# spider-som.net
KiCad netlist of a schematic drawn in Altium Designer
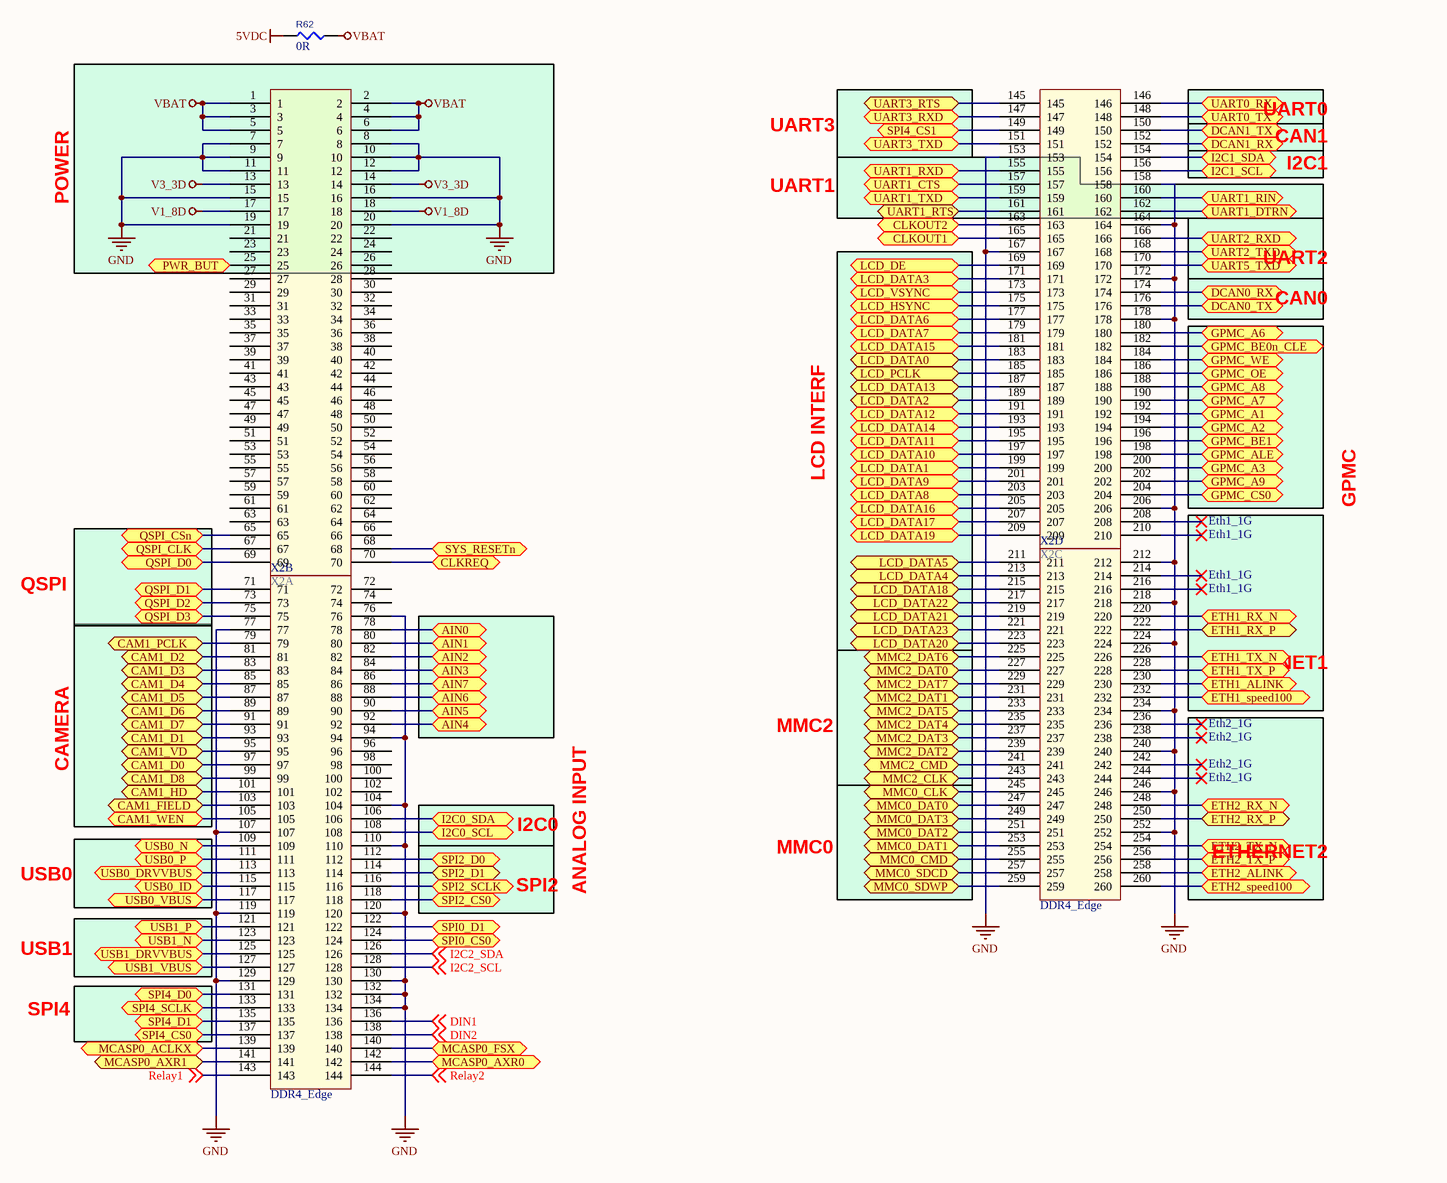
[diagram p0: spider-som.SchDoc]

(export (version "E")
  (design (tool "Eeschema 10.0.6"))
  (components
    (comp (ref "R62")
      (value "0R")
      (footprint "RESC1608X55N")
      (description "R0603")
      (libsource (lib "spider") (part "R0603"))
    )
    (comp (ref "X2")
      (value "DDR4_Edge")
      (footprint "DDR4 SO_DIMM connector")
      (description "DDR4 edge memory SO-DIMM connector, 260 pin")
      (libsource (lib "spider") (part "DDR4_Edge"))
    )
  )
  (nets
    (net (code "1") (name "/AIN0") (class "Default")
      (node (ref "X2") (pin "78") (pinfunction "78_78") (pintype "passive"))
    )
    (net (code "2") (name "/AIN1") (class "Default")
      (node (ref "X2") (pin "80") (pinfunction "80_80") (pintype "passive"))
    )
    (net (code "3") (name "/AIN2") (class "Default")
      (node (ref "X2") (pin "82") (pinfunction "82_82") (pintype "passive"))
    )
    (net (code "4") (name "/AIN3") (class "Default")
      (node (ref "X2") (pin "84") (pinfunction "84_84") (pintype "passive"))
    )
    (net (code "5") (name "/AIN4") (class "Default")
      (node (ref "X2") (pin "92") (pinfunction "92_92") (pintype "passive"))
    )
    (net (code "6") (name "/AIN5") (class "Default")
      (node (ref "X2") (pin "90") (pinfunction "90_90") (pintype "passive"))
    )
    (net (code "7") (name "/AIN6") (class "Default")
      (node (ref "X2") (pin "88") (pinfunction "88_88") (pintype "passive"))
    )
    (net (code "8") (name "/AIN7") (class "Default")
      (node (ref "X2") (pin "86") (pinfunction "86_86") (pintype "passive"))
    )
    (net (code "9") (name "/CAM1_D0") (class "Default")
      (node (ref "X2") (pin "97") (pinfunction "97_97") (pintype "passive"))
    )
    (net (code "10") (name "/CAM1_D1") (class "Default")
      (node (ref "X2") (pin "93") (pinfunction "93_93") (pintype "passive"))
    )
    (net (code "11") (name "/CAM1_D2") (class "Default")
      (node (ref "X2") (pin "81") (pinfunction "81_81") (pintype "passive"))
    )
    (net (code "12") (name "/CAM1_D3") (class "Default")
      (node (ref "X2") (pin "83") (pinfunction "83_83") (pintype "passive"))
    )
    (net (code "13") (name "/CAM1_D4") (class "Default")
      (node (ref "X2") (pin "85") (pinfunction "85_85") (pintype "passive"))
    )
    (net (code "14") (name "/CAM1_D5") (class "Default")
      (node (ref "X2") (pin "87") (pinfunction "87_87") (pintype "passive"))
    )
    (net (code "15") (name "/CAM1_D6") (class "Default")
      (node (ref "X2") (pin "89") (pinfunction "89_89") (pintype "passive"))
    )
    (net (code "16") (name "/CAM1_D7") (class "Default")
      (node (ref "X2") (pin "91") (pinfunction "91_91") (pintype "passive"))
    )
    (net (code "17") (name "/CAM1_D8") (class "Default")
      (node (ref "X2") (pin "99") (pinfunction "99_99") (pintype "passive"))
    )
    (net (code "18") (name "/CAM1_FIELD") (class "Default")
      (node (ref "X2") (pin "103") (pinfunction "103_103") (pintype "passive"))
    )
    (net (code "19") (name "/CAM1_HD") (class "Default")
      (node (ref "X2") (pin "101") (pinfunction "101_101") (pintype "passive"))
    )
    (net (code "20") (name "/CAM1_PCLK") (class "Default")
      (node (ref "X2") (pin "79") (pinfunction "79_79") (pintype "passive"))
    )
    (net (code "21") (name "/CAM1_VD") (class "Default")
      (node (ref "X2") (pin "95") (pinfunction "95_95") (pintype "passive"))
    )
    (net (code "22") (name "/CAM1_WEN") (class "Default")
      (node (ref "X2") (pin "105") (pinfunction "105_105") (pintype "passive"))
    )
    (net (code "23") (name "/CLKOUT1") (class "Default")
      (node (ref "X2") (pin "165") (pinfunction "165_165") (pintype "passive"))
    )
    (net (code "24") (name "/CLKOUT2") (class "Default")
      (node (ref "X2") (pin "163") (pinfunction "163_163") (pintype "passive"))
    )
    (net (code "25") (name "/CLKREQ") (class "Default")
      (node (ref "X2") (pin "70") (pinfunction "70_70") (pintype "passive"))
    )
    (net (code "26") (name "/DCAN0_RX") (class "Default")
      (node (ref "X2") (pin "174") (pinfunction "174_174") (pintype "passive"))
    )
    (net (code "27") (name "/DCAN0_TX") (class "Default")
      (node (ref "X2") (pin "176") (pinfunction "176_176") (pintype "passive"))
    )
    (net (code "28") (name "/DCAN1_RX") (class "Default")
      (node (ref "X2") (pin "152") (pinfunction "152_152") (pintype "passive"))
    )
    (net (code "29") (name "/DCAN1_TX") (class "Default")
      (node (ref "X2") (pin "150") (pinfunction "150_150") (pintype "passive"))
    )
    (net (code "30") (name "/ETH1_ALINK") (class "Default")
      (node (ref "X2") (pin "230") (pinfunction "230_230") (pintype "passive"))
    )
    (net (code "31") (name "/ETH1_RX_N") (class "Default")
      (node (ref "X2") (pin "220") (pinfunction "220_220") (pintype "passive"))
    )
    (net (code "32") (name "/ETH1_RX_P") (class "Default")
      (node (ref "X2") (pin "222") (pinfunction "222_222") (pintype "passive"))
    )
    (net (code "33") (name "/ETH1_TX_N") (class "Default")
      (node (ref "X2") (pin "226") (pinfunction "226_226") (pintype "passive"))
    )
    (net (code "34") (name "/ETH1_TX_P") (class "Default")
      (node (ref "X2") (pin "228") (pinfunction "228_228") (pintype "passive"))
    )
    (net (code "35") (name "/ETH1_speed100") (class "Default")
      (node (ref "X2") (pin "232") (pinfunction "232_232") (pintype "passive"))
    )
    (net (code "36") (name "/ETH2_ALINK") (class "Default")
      (node (ref "X2") (pin "258") (pinfunction "258_258") (pintype "passive"))
    )
    (net (code "37") (name "/ETH2_RX_N") (class "Default")
      (node (ref "X2") (pin "248") (pinfunction "248_248") (pintype "passive"))
    )
    (net (code "38") (name "/ETH2_RX_P") (class "Default")
      (node (ref "X2") (pin "250") (pinfunction "250_250") (pintype "passive"))
    )
    (net (code "39") (name "/ETH2_TX_N") (class "Default")
      (node (ref "X2") (pin "254") (pinfunction "254_254") (pintype "passive"))
    )
    (net (code "40") (name "/ETH2_TX_P") (class "Default")
      (node (ref "X2") (pin "256") (pinfunction "256_256") (pintype "passive"))
    )
    (net (code "41") (name "/ETH2_speed100") (class "Default")
      (node (ref "X2") (pin "260") (pinfunction "260_260") (pintype "passive"))
    )
    (net (code "42") (name "/GPMC_A1") (class "Default")
      (node (ref "X2") (pin "192") (pinfunction "192_192") (pintype "passive"))
    )
    (net (code "43") (name "/GPMC_A2") (class "Default")
      (node (ref "X2") (pin "194") (pinfunction "194_194") (pintype "passive"))
    )
    (net (code "44") (name "/GPMC_A3") (class "Default")
      (node (ref "X2") (pin "200") (pinfunction "200_200") (pintype "passive"))
    )
    (net (code "45") (name "/GPMC_A6") (class "Default")
      (node (ref "X2") (pin "180") (pinfunction "180_180") (pintype "passive"))
    )
    (net (code "46") (name "/GPMC_A7") (class "Default")
      (node (ref "X2") (pin "190") (pinfunction "190_190") (pintype "passive"))
    )
    (net (code "47") (name "/GPMC_A8") (class "Default")
      (node (ref "X2") (pin "188") (pinfunction "188_188") (pintype "passive"))
    )
    (net (code "48") (name "/GPMC_A9") (class "Default")
      (node (ref "X2") (pin "202") (pinfunction "202_202") (pintype "passive"))
    )
    (net (code "49") (name "/GPMC_ALE") (class "Default")
      (node (ref "X2") (pin "198") (pinfunction "198_198") (pintype "passive"))
    )
    (net (code "50") (name "/GPMC_BE0n_CLE") (class "Default")
      (node (ref "X2") (pin "182") (pinfunction "182_182") (pintype "passive"))
    )
    (net (code "51") (name "/GPMC_BE1") (class "Default")
      (node (ref "X2") (pin "196") (pinfunction "196_196") (pintype "passive"))
    )
    (net (code "52") (name "/GPMC_CS0") (class "Default")
      (node (ref "X2") (pin "204") (pinfunction "204_204") (pintype "passive"))
    )
    (net (code "53") (name "/GPMC_OE") (class "Default")
      (node (ref "X2") (pin "186") (pinfunction "186_186") (pintype "passive"))
    )
    (net (code "54") (name "/GPMC_WE") (class "Default")
      (node (ref "X2") (pin "184") (pinfunction "184_184") (pintype "passive"))
    )
    (net (code "55") (name "/I2C0_SCL") (class "Default")
      (node (ref "X2") (pin "108") (pinfunction "108_108") (pintype "passive"))
    )
    (net (code "56") (name "/I2C0_SDA") (class "Default")
      (node (ref "X2") (pin "106") (pinfunction "106_106") (pintype "passive"))
    )
    (net (code "57") (name "/I2C1_SCL") (class "Default")
      (node (ref "X2") (pin "156") (pinfunction "156_156") (pintype "passive"))
    )
    (net (code "58") (name "/I2C1_SDA") (class "Default")
      (node (ref "X2") (pin "154") (pinfunction "154_154") (pintype "passive"))
    )
    (net (code "59") (name "/LCD_DATA0") (class "Default")
      (node (ref "X2") (pin "183") (pinfunction "183_183") (pintype "passive"))
    )
    (net (code "60") (name "/LCD_DATA1") (class "Default")
      (node (ref "X2") (pin "199") (pinfunction "199_199") (pintype "passive"))
    )
    (net (code "61") (name "/LCD_DATA2") (class "Default")
      (node (ref "X2") (pin "189") (pinfunction "189_189") (pintype "passive"))
    )
    (net (code "62") (name "/LCD_DATA3") (class "Default")
      (node (ref "X2") (pin "171") (pinfunction "171_171") (pintype "passive"))
    )
    (net (code "63") (name "/LCD_DATA4") (class "Default")
      (node (ref "X2") (pin "213") (pinfunction "213_213") (pintype "passive"))
    )
    (net (code "64") (name "/LCD_DATA5") (class "Default")
      (node (ref "X2") (pin "211") (pinfunction "211_211") (pintype "passive"))
    )
    (net (code "65") (name "/LCD_DATA6") (class "Default")
      (node (ref "X2") (pin "177") (pinfunction "177_177") (pintype "passive"))
    )
    (net (code "66") (name "/LCD_DATA7") (class "Default")
      (node (ref "X2") (pin "179") (pinfunction "179_179") (pintype "passive"))
    )
    (net (code "67") (name "/LCD_DATA8") (class "Default")
      (node (ref "X2") (pin "203") (pinfunction "203_203") (pintype "passive"))
    )
    (net (code "68") (name "/LCD_DATA9") (class "Default")
      (node (ref "X2") (pin "201") (pinfunction "201_201") (pintype "passive"))
    )
    (net (code "69") (name "/LCD_DATA10") (class "Default")
      (node (ref "X2") (pin "197") (pinfunction "197_197") (pintype "passive"))
    )
    (net (code "70") (name "/LCD_DATA11") (class "Default")
      (node (ref "X2") (pin "195") (pinfunction "195_195") (pintype "passive"))
    )
    (net (code "71") (name "/LCD_DATA12") (class "Default")
      (node (ref "X2") (pin "191") (pinfunction "191_191") (pintype "passive"))
    )
    (net (code "72") (name "/LCD_DATA13") (class "Default")
      (node (ref "X2") (pin "187") (pinfunction "187_187") (pintype "passive"))
    )
    (net (code "73") (name "/LCD_DATA14") (class "Default")
      (node (ref "X2") (pin "193") (pinfunction "193_193") (pintype "passive"))
    )
    (net (code "74") (name "/LCD_DATA15") (class "Default")
      (node (ref "X2") (pin "181") (pinfunction "181_181") (pintype "passive"))
    )
    (net (code "75") (name "/LCD_DATA16") (class "Default")
      (node (ref "X2") (pin "205") (pinfunction "205_205") (pintype "passive"))
    )
    (net (code "76") (name "/LCD_DATA17") (class "Default")
      (node (ref "X2") (pin "207") (pinfunction "207_207") (pintype "passive"))
    )
    (net (code "77") (name "/LCD_DATA18") (class "Default")
      (node (ref "X2") (pin "215") (pinfunction "215_215") (pintype "passive"))
    )
    (net (code "78") (name "/LCD_DATA19") (class "Default")
      (node (ref "X2") (pin "209") (pinfunction "209_209") (pintype "passive"))
    )
    (net (code "79") (name "/LCD_DATA20") (class "Default")
      (node (ref "X2") (pin "223") (pinfunction "223_223") (pintype "passive"))
    )
    (net (code "80") (name "/LCD_DATA21") (class "Default")
      (node (ref "X2") (pin "219") (pinfunction "219_219") (pintype "passive"))
    )
    (net (code "81") (name "/LCD_DATA22") (class "Default")
      (node (ref "X2") (pin "217") (pinfunction "217_217") (pintype "passive"))
    )
    (net (code "82") (name "/LCD_DATA23") (class "Default")
      (node (ref "X2") (pin "221") (pinfunction "221_221") (pintype "passive"))
    )
    (net (code "83") (name "/LCD_DE") (class "Default")
      (node (ref "X2") (pin "169") (pinfunction "169_169") (pintype "passive"))
    )
    (net (code "84") (name "/LCD_HSYNC") (class "Default")
      (node (ref "X2") (pin "175") (pinfunction "175_175") (pintype "passive"))
    )
    (net (code "85") (name "/LCD_PCLK") (class "Default")
      (node (ref "X2") (pin "185") (pinfunction "185_185") (pintype "passive"))
    )
    (net (code "86") (name "/LCD_VSYNC") (class "Default")
      (node (ref "X2") (pin "173") (pinfunction "173_173") (pintype "passive"))
    )
    (net (code "87") (name "/MCASP0_ACLKX") (class "Default")
      (node (ref "X2") (pin "139") (pinfunction "139_139") (pintype "passive"))
    )
    (net (code "88") (name "/MCASP0_AXR0") (class "Default")
      (node (ref "X2") (pin "142") (pinfunction "142_142") (pintype "passive"))
    )
    (net (code "89") (name "/MCASP0_AXR1") (class "Default")
      (node (ref "X2") (pin "141") (pinfunction "141_141") (pintype "passive"))
    )
    (net (code "90") (name "/MCASP0_FSX") (class "Default")
      (node (ref "X2") (pin "140") (pinfunction "140_140") (pintype "passive"))
    )
    (net (code "91") (name "/MMC0_CLK") (class "Default")
      (node (ref "X2") (pin "245") (pinfunction "245_245") (pintype "passive"))
    )
    (net (code "92") (name "/MMC0_CMD") (class "Default")
      (node (ref "X2") (pin "255") (pinfunction "255_255") (pintype "passive"))
    )
    (net (code "93") (name "/MMC0_DAT0") (class "Default")
      (node (ref "X2") (pin "247") (pinfunction "247_247") (pintype "passive"))
    )
    (net (code "94") (name "/MMC0_DAT1") (class "Default")
      (node (ref "X2") (pin "253") (pinfunction "253_253") (pintype "passive"))
    )
    (net (code "95") (name "/MMC0_DAT2") (class "Default")
      (node (ref "X2") (pin "251") (pinfunction "251_251") (pintype "passive"))
    )
    (net (code "96") (name "/MMC0_DAT3") (class "Default")
      (node (ref "X2") (pin "249") (pinfunction "249_249") (pintype "passive"))
    )
    (net (code "97") (name "/MMC0_SDCD") (class "Default")
      (node (ref "X2") (pin "257") (pinfunction "257_257") (pintype "passive"))
    )
    (net (code "98") (name "/MMC0_SDWP") (class "Default")
      (node (ref "X2") (pin "259") (pinfunction "259_259") (pintype "passive"))
    )
    (net (code "99") (name "/MMC2_CLK") (class "Default")
      (node (ref "X2") (pin "243") (pinfunction "243_243") (pintype "passive"))
    )
    (net (code "100") (name "/MMC2_CMD") (class "Default")
      (node (ref "X2") (pin "241") (pinfunction "241_241") (pintype "passive"))
    )
    (net (code "101") (name "/MMC2_DAT0") (class "Default")
      (node (ref "X2") (pin "227") (pinfunction "227_227") (pintype "passive"))
    )
    (net (code "102") (name "/MMC2_DAT1") (class "Default")
      (node (ref "X2") (pin "231") (pinfunction "231_231") (pintype "passive"))
    )
    (net (code "103") (name "/MMC2_DAT2") (class "Default")
      (node (ref "X2") (pin "239") (pinfunction "239_239") (pintype "passive"))
    )
    (net (code "104") (name "/MMC2_DAT3") (class "Default")
      (node (ref "X2") (pin "237") (pinfunction "237_237") (pintype "passive"))
    )
    (net (code "105") (name "/MMC2_DAT4") (class "Default")
      (node (ref "X2") (pin "235") (pinfunction "235_235") (pintype "passive"))
    )
    (net (code "106") (name "/MMC2_DAT5") (class "Default")
      (node (ref "X2") (pin "233") (pinfunction "233_233") (pintype "passive"))
    )
    (net (code "107") (name "/MMC2_DAT6") (class "Default")
      (node (ref "X2") (pin "225") (pinfunction "225_225") (pintype "passive"))
    )
    (net (code "108") (name "/MMC2_DAT7") (class "Default")
      (node (ref "X2") (pin "229") (pinfunction "229_229") (pintype "passive"))
    )
    (net (code "109") (name "/PWR_BUT") (class "Default")
      (node (ref "X2") (pin "25") (pinfunction "25_25") (pintype "passive"))
    )
    (net (code "110") (name "/QSPI_CLK") (class "Default")
      (node (ref "X2") (pin "67") (pinfunction "67_67") (pintype "passive"))
    )
    (net (code "111") (name "/QSPI_CSn") (class "Default")
      (node (ref "X2") (pin "65") (pinfunction "65_65") (pintype "passive"))
    )
    (net (code "112") (name "/QSPI_D0") (class "Default")
      (node (ref "X2") (pin "69") (pinfunction "69_69") (pintype "passive"))
    )
    (net (code "113") (name "/QSPI_D1") (class "Default")
      (node (ref "X2") (pin "71") (pinfunction "71_71") (pintype "passive"))
    )
    (net (code "114") (name "/QSPI_D2") (class "Default")
      (node (ref "X2") (pin "73") (pinfunction "73_73") (pintype "passive"))
    )
    (net (code "115") (name "/QSPI_D3") (class "Default")
      (node (ref "X2") (pin "75") (pinfunction "75_75") (pintype "passive"))
    )
    (net (code "116") (name "/SPI0_CS0") (class "Default")
      (node (ref "X2") (pin "124") (pinfunction "124_124") (pintype "passive"))
    )
    (net (code "117") (name "/SPI0_D1") (class "Default")
      (node (ref "X2") (pin "122") (pinfunction "122_122") (pintype "passive"))
    )
    (net (code "118") (name "/SPI2_CS0") (class "Default")
      (node (ref "X2") (pin "118") (pinfunction "118_118") (pintype "passive"))
    )
    (net (code "119") (name "/SPI2_D0") (class "Default")
      (node (ref "X2") (pin "112") (pinfunction "112_112") (pintype "passive"))
    )
    (net (code "120") (name "/SPI2_D1") (class "Default")
      (node (ref "X2") (pin "114") (pinfunction "114_114") (pintype "passive"))
    )
    (net (code "121") (name "/SPI2_SCLK") (class "Default")
      (node (ref "X2") (pin "116") (pinfunction "116_116") (pintype "passive"))
    )
    (net (code "122") (name "/SPI4_CS0") (class "Default")
      (node (ref "X2") (pin "137") (pinfunction "137_137") (pintype "passive"))
    )
    (net (code "123") (name "/SPI4_CS1") (class "Default")
      (node (ref "X2") (pin "149") (pinfunction "149_149") (pintype "passive"))
    )
    (net (code "124") (name "/SPI4_D0") (class "Default")
      (node (ref "X2") (pin "131") (pinfunction "131_131") (pintype "passive"))
    )
    (net (code "125") (name "/SPI4_D1") (class "Default")
      (node (ref "X2") (pin "135") (pinfunction "135_135") (pintype "passive"))
    )
    (net (code "126") (name "/SPI4_SCLK") (class "Default")
      (node (ref "X2") (pin "133") (pinfunction "133_133") (pintype "passive"))
    )
    (net (code "127") (name "/SYS_RESETn") (class "Default")
      (node (ref "X2") (pin "68") (pinfunction "68_68") (pintype "passive"))
    )
    (net (code "128") (name "/UART0_RX") (class "Default")
      (node (ref "X2") (pin "146") (pinfunction "146_146") (pintype "passive"))
    )
    (net (code "129") (name "/UART0_TX") (class "Default")
      (node (ref "X2") (pin "148") (pinfunction "148_148") (pintype "passive"))
    )
    (net (code "130") (name "/UART1_CTS") (class "Default")
      (node (ref "X2") (pin "157") (pinfunction "157_157") (pintype "passive"))
    )
    (net (code "131") (name "/UART1_DTRN") (class "Default")
      (node (ref "X2") (pin "162") (pinfunction "162_162") (pintype "passive"))
    )
    (net (code "132") (name "/UART1_RIN") (class "Default")
      (node (ref "X2") (pin "160") (pinfunction "160_160") (pintype "passive"))
    )
    (net (code "133") (name "/UART1_RTS") (class "Default")
      (node (ref "X2") (pin "161") (pinfunction "161_161") (pintype "passive"))
    )
    (net (code "134") (name "/UART1_RXD") (class "Default")
      (node (ref "X2") (pin "155") (pinfunction "155_155") (pintype "passive"))
    )
    (net (code "135") (name "/UART1_TXD") (class "Default")
      (node (ref "X2") (pin "159") (pinfunction "159_159") (pintype "passive"))
    )
    (net (code "136") (name "/UART2_RXD") (class "Default")
      (node (ref "X2") (pin "166") (pinfunction "166_166") (pintype "passive"))
    )
    (net (code "137") (name "/UART2_TXD") (class "Default")
      (node (ref "X2") (pin "168") (pinfunction "168_168") (pintype "passive"))
    )
    (net (code "138") (name "/UART3_RTS") (class "Default")
      (node (ref "X2") (pin "145") (pinfunction "145_145") (pintype "passive"))
    )
    (net (code "139") (name "/UART3_RXD") (class "Default")
      (node (ref "X2") (pin "147") (pinfunction "147_147") (pintype "passive"))
    )
    (net (code "140") (name "/UART3_TXD") (class "Default")
      (node (ref "X2") (pin "151") (pinfunction "151_151") (pintype "passive"))
    )
    (net (code "141") (name "/UART5_TXD") (class "Default")
      (node (ref "X2") (pin "170") (pinfunction "170_170") (pintype "passive"))
    )
    (net (code "142") (name "/USB0_DRVVBUS") (class "Default")
      (node (ref "X2") (pin "113") (pinfunction "113_113") (pintype "passive"))
    )
    (net (code "143") (name "/USB0_ID") (class "Default")
      (node (ref "X2") (pin "115") (pinfunction "115_115") (pintype "passive"))
    )
    (net (code "144") (name "/USB0_N") (class "Default")
      (node (ref "X2") (pin "109") (pinfunction "109_109") (pintype "passive"))
    )
    (net (code "145") (name "/USB0_P") (class "Default")
      (node (ref "X2") (pin "111") (pinfunction "111_111") (pintype "passive"))
    )
    (net (code "146") (name "/USB0_VBUS") (class "Default")
      (node (ref "X2") (pin "117") (pinfunction "117_117") (pintype "passive"))
    )
    (net (code "147") (name "/USB1_DRVVBUS") (class "Default")
      (node (ref "X2") (pin "125") (pinfunction "125_125") (pintype "passive"))
    )
    (net (code "148") (name "/USB1_N") (class "Default")
      (node (ref "X2") (pin "123") (pinfunction "123_123") (pintype "passive"))
    )
    (net (code "149") (name "/USB1_P") (class "Default")
      (node (ref "X2") (pin "121") (pinfunction "121_121") (pintype "passive"))
    )
    (net (code "150") (name "/USB1_VBUS") (class "Default")
      (node (ref "X2") (pin "127") (pinfunction "127_127") (pintype "passive"))
    )
    (net (code "151") (name "5VDC") (class "Default")
      (node (ref "R62") (pin "1") (pinfunction "1_1") (pintype "passive"))
    )
    (net (code "152") (name "DIN1") (class "Default")
      (node (ref "X2") (pin "136") (pinfunction "136_136") (pintype "passive"))
    )
    (net (code "153") (name "DIN2") (class "Default")
      (node (ref "X2") (pin "138") (pinfunction "138_138") (pintype "passive"))
    )
    (net (code "154") (name "GND") (class "Default")
      (node (ref "X2") (pin "10") (pinfunction "10_10") (pintype "passive"))
      (node (ref "X2") (pin "104") (pinfunction "104_104") (pintype "passive"))
      (node (ref "X2") (pin "107") (pinfunction "107_107") (pintype "passive"))
      (node (ref "X2") (pin "11") (pinfunction "11_11") (pintype "passive"))
      (node (ref "X2") (pin "110") (pinfunction "110_110") (pintype "passive"))
      (node (ref "X2") (pin "119") (pinfunction "119_119") (pintype "passive"))
      (node (ref "X2") (pin "12") (pinfunction "12_12") (pintype "passive"))
      (node (ref "X2") (pin "120") (pinfunction "120_120") (pintype "passive"))
      (node (ref "X2") (pin "129") (pinfunction "129_129") (pintype "passive"))
      (node (ref "X2") (pin "130") (pinfunction "130_130") (pintype "passive"))
      (node (ref "X2") (pin "132") (pinfunction "132_132") (pintype "passive"))
      (node (ref "X2") (pin "134") (pinfunction "134_134") (pintype "passive"))
      (node (ref "X2") (pin "15") (pinfunction "15_15") (pintype "passive"))
      (node (ref "X2") (pin "153") (pinfunction "153_153") (pintype "passive"))
      (node (ref "X2") (pin "158") (pinfunction "158_158") (pintype "passive"))
      (node (ref "X2") (pin "16") (pinfunction "16_16") (pintype "passive"))
      (node (ref "X2") (pin "164") (pinfunction "164_164") (pintype "passive"))
      (node (ref "X2") (pin "167") (pinfunction "167_167") (pintype "passive"))
      (node (ref "X2") (pin "172") (pinfunction "172_172") (pintype "passive"))
      (node (ref "X2") (pin "178") (pinfunction "178_178") (pintype "passive"))
      (node (ref "X2") (pin "19") (pinfunction "19_19") (pintype "passive"))
      (node (ref "X2") (pin "20") (pinfunction "20_20") (pintype "passive"))
      (node (ref "X2") (pin "206") (pinfunction "206_206") (pintype "passive"))
      (node (ref "X2") (pin "212") (pinfunction "212_212") (pintype "passive"))
      (node (ref "X2") (pin "218") (pinfunction "218_218") (pintype "passive"))
      (node (ref "X2") (pin "224") (pinfunction "224_224") (pintype "passive"))
      (node (ref "X2") (pin "234") (pinfunction "234_234") (pintype "passive"))
      (node (ref "X2") (pin "240") (pinfunction "240_240") (pintype "passive"))
      (node (ref "X2") (pin "246") (pinfunction "246_246") (pintype "passive"))
      (node (ref "X2") (pin "252") (pinfunction "252_252") (pintype "passive"))
      (node (ref "X2") (pin "7") (pinfunction "7_7") (pintype "passive"))
      (node (ref "X2") (pin "76") (pinfunction "76_76") (pintype "passive"))
      (node (ref "X2") (pin "77") (pinfunction "77_77") (pintype "passive"))
      (node (ref "X2") (pin "8") (pinfunction "8_8") (pintype "passive"))
      (node (ref "X2") (pin "9") (pinfunction "9_9") (pintype "passive"))
      (node (ref "X2") (pin "94") (pinfunction "94_94") (pintype "passive"))
    )
    (net (code "155") (name "I2C2_SCL") (class "Default")
      (node (ref "X2") (pin "128") (pinfunction "128_128") (pintype "passive"))
    )
    (net (code "156") (name "I2C2_SDA") (class "Default")
      (node (ref "X2") (pin "126") (pinfunction "126_126") (pintype "passive"))
    )
    (net (code "157") (name "Relay1") (class "Default")
      (node (ref "X2") (pin "143") (pinfunction "143_143") (pintype "passive"))
    )
    (net (code "158") (name "Relay2") (class "Default")
      (node (ref "X2") (pin "144") (pinfunction "144_144") (pintype "passive"))
    )
    (net (code "159") (name "V1_8D") (class "Default")
      (node (ref "X2") (pin "17") (pinfunction "17_17") (pintype "passive"))
      (node (ref "X2") (pin "18") (pinfunction "18_18") (pintype "passive"))
    )
    (net (code "160") (name "V3_3D") (class "Default")
      (node (ref "X2") (pin "13") (pinfunction "13_13") (pintype "passive"))
      (node (ref "X2") (pin "14") (pinfunction "14_14") (pintype "passive"))
    )
    (net (code "161") (name "VBAT") (class "Default")
      (node (ref "R62") (pin "2") (pinfunction "2_2") (pintype "passive"))
      (node (ref "X2") (pin "1") (pinfunction "1_1") (pintype "passive"))
      (node (ref "X2") (pin "2") (pinfunction "2_2") (pintype "passive"))
      (node (ref "X2") (pin "3") (pinfunction "3_3") (pintype "passive"))
      (node (ref "X2") (pin "4") (pinfunction "4_4") (pintype "passive"))
      (node (ref "X2") (pin "5") (pinfunction "5_5") (pintype "passive"))
      (node (ref "X2") (pin "6") (pinfunction "6_6") (pintype "passive"))
    )
    (net (code "162") (name "unconnected-(X2-Pad21)") (class "Default")
      (node (ref "X2") (pin "21") (pinfunction "21_21") (pintype "passive"))
    )
    (net (code "163") (name "unconnected-(X2-Pad22)") (class "Default")
      (node (ref "X2") (pin "22") (pinfunction "22_22") (pintype "passive"))
    )
    (net (code "164") (name "unconnected-(X2-Pad23)") (class "Default")
      (node (ref "X2") (pin "23") (pinfunction "23_23") (pintype "passive"))
    )
    (net (code "165") (name "unconnected-(X2-Pad24)") (class "Default")
      (node (ref "X2") (pin "24") (pinfunction "24_24") (pintype "passive"))
    )
    (net (code "166") (name "unconnected-(X2-Pad26)") (class "Default")
      (node (ref "X2") (pin "26") (pinfunction "26_26") (pintype "passive"))
    )
    (net (code "167") (name "unconnected-(X2-Pad27)") (class "Default")
      (node (ref "X2") (pin "27") (pinfunction "27_27") (pintype "passive"))
    )
    (net (code "168") (name "unconnected-(X2-Pad28)") (class "Default")
      (node (ref "X2") (pin "28") (pinfunction "28_28") (pintype "passive"))
    )
    (net (code "169") (name "unconnected-(X2-Pad29)") (class "Default")
      (node (ref "X2") (pin "29") (pinfunction "29_29") (pintype "passive"))
    )
    (net (code "170") (name "unconnected-(X2-Pad30)") (class "Default")
      (node (ref "X2") (pin "30") (pinfunction "30_30") (pintype "passive"))
    )
    (net (code "171") (name "unconnected-(X2-Pad31)") (class "Default")
      (node (ref "X2") (pin "31") (pinfunction "31_31") (pintype "passive"))
    )
    (net (code "172") (name "unconnected-(X2-Pad32)") (class "Default")
      (node (ref "X2") (pin "32") (pinfunction "32_32") (pintype "passive"))
    )
    (net (code "173") (name "unconnected-(X2-Pad33)") (class "Default")
      (node (ref "X2") (pin "33") (pinfunction "33_33") (pintype "passive"))
    )
    (net (code "174") (name "unconnected-(X2-Pad34)") (class "Default")
      (node (ref "X2") (pin "34") (pinfunction "34_34") (pintype "passive"))
    )
    (net (code "175") (name "unconnected-(X2-Pad35)") (class "Default")
      (node (ref "X2") (pin "35") (pinfunction "35_35") (pintype "passive"))
    )
    (net (code "176") (name "unconnected-(X2-Pad36)") (class "Default")
      (node (ref "X2") (pin "36") (pinfunction "36_36") (pintype "passive"))
    )
    (net (code "177") (name "unconnected-(X2-Pad37)") (class "Default")
      (node (ref "X2") (pin "37") (pinfunction "37_37") (pintype "passive"))
    )
    (net (code "178") (name "unconnected-(X2-Pad38)") (class "Default")
      (node (ref "X2") (pin "38") (pinfunction "38_38") (pintype "passive"))
    )
    (net (code "179") (name "unconnected-(X2-Pad39)") (class "Default")
      (node (ref "X2") (pin "39") (pinfunction "39_39") (pintype "passive"))
    )
    (net (code "180") (name "unconnected-(X2-Pad40)") (class "Default")
      (node (ref "X2") (pin "40") (pinfunction "40_40") (pintype "passive"))
    )
    (net (code "181") (name "unconnected-(X2-Pad41)") (class "Default")
      (node (ref "X2") (pin "41") (pinfunction "41_41") (pintype "passive"))
    )
    (net (code "182") (name "unconnected-(X2-Pad42)") (class "Default")
      (node (ref "X2") (pin "42") (pinfunction "42_42") (pintype "passive"))
    )
    (net (code "183") (name "unconnected-(X2-Pad43)") (class "Default")
      (node (ref "X2") (pin "43") (pinfunction "43_43") (pintype "passive"))
    )
    (net (code "184") (name "unconnected-(X2-Pad44)") (class "Default")
      (node (ref "X2") (pin "44") (pinfunction "44_44") (pintype "passive"))
    )
    (net (code "185") (name "unconnected-(X2-Pad45)") (class "Default")
      (node (ref "X2") (pin "45") (pinfunction "45_45") (pintype "passive"))
    )
    (net (code "186") (name "unconnected-(X2-Pad46)") (class "Default")
      (node (ref "X2") (pin "46") (pinfunction "46_46") (pintype "passive"))
    )
    (net (code "187") (name "unconnected-(X2-Pad47)") (class "Default")
      (node (ref "X2") (pin "47") (pinfunction "47_47") (pintype "passive"))
    )
    (net (code "188") (name "unconnected-(X2-Pad48)") (class "Default")
      (node (ref "X2") (pin "48") (pinfunction "48_48") (pintype "passive"))
    )
    (net (code "189") (name "unconnected-(X2-Pad49)") (class "Default")
      (node (ref "X2") (pin "49") (pinfunction "49_49") (pintype "passive"))
    )
    (net (code "190") (name "unconnected-(X2-Pad50)") (class "Default")
      (node (ref "X2") (pin "50") (pinfunction "50_50") (pintype "passive"))
    )
    (net (code "191") (name "unconnected-(X2-Pad51)") (class "Default")
      (node (ref "X2") (pin "51") (pinfunction "51_51") (pintype "passive"))
    )
    (net (code "192") (name "unconnected-(X2-Pad52)") (class "Default")
      (node (ref "X2") (pin "52") (pinfunction "52_52") (pintype "passive"))
    )
    (net (code "193") (name "unconnected-(X2-Pad53)") (class "Default")
      (node (ref "X2") (pin "53") (pinfunction "53_53") (pintype "passive"))
    )
    (net (code "194") (name "unconnected-(X2-Pad54)") (class "Default")
      (node (ref "X2") (pin "54") (pinfunction "54_54") (pintype "passive"))
    )
    (net (code "195") (name "unconnected-(X2-Pad55)") (class "Default")
      (node (ref "X2") (pin "55") (pinfunction "55_55") (pintype "passive"))
    )
    (net (code "196") (name "unconnected-(X2-Pad56)") (class "Default")
      (node (ref "X2") (pin "56") (pinfunction "56_56") (pintype "passive"))
    )
    (net (code "197") (name "unconnected-(X2-Pad57)") (class "Default")
      (node (ref "X2") (pin "57") (pinfunction "57_57") (pintype "passive"))
    )
    (net (code "198") (name "unconnected-(X2-Pad58)") (class "Default")
      (node (ref "X2") (pin "58") (pinfunction "58_58") (pintype "passive"))
    )
    (net (code "199") (name "unconnected-(X2-Pad59)") (class "Default")
      (node (ref "X2") (pin "59") (pinfunction "59_59") (pintype "passive"))
    )
    (net (code "200") (name "unconnected-(X2-Pad60)") (class "Default")
      (node (ref "X2") (pin "60") (pinfunction "60_60") (pintype "passive"))
    )
    (net (code "201") (name "unconnected-(X2-Pad61)") (class "Default")
      (node (ref "X2") (pin "61") (pinfunction "61_61") (pintype "passive"))
    )
    (net (code "202") (name "unconnected-(X2-Pad62)") (class "Default")
      (node (ref "X2") (pin "62") (pinfunction "62_62") (pintype "passive"))
    )
    (net (code "203") (name "unconnected-(X2-Pad63)") (class "Default")
      (node (ref "X2") (pin "63") (pinfunction "63_63") (pintype "passive"))
    )
    (net (code "204") (name "unconnected-(X2-Pad64)") (class "Default")
      (node (ref "X2") (pin "64") (pinfunction "64_64") (pintype "passive"))
    )
    (net (code "205") (name "unconnected-(X2-Pad66)") (class "Default")
      (node (ref "X2") (pin "66") (pinfunction "66_66") (pintype "passive"))
    )
    (net (code "206") (name "unconnected-(X2-Pad72)") (class "Default")
      (node (ref "X2") (pin "72") (pinfunction "72_72") (pintype "passive"))
    )
    (net (code "207") (name "unconnected-(X2-Pad74)") (class "Default")
      (node (ref "X2") (pin "74") (pinfunction "74_74") (pintype "passive"))
    )
    (net (code "208") (name "unconnected-(X2-Pad96)") (class "Default")
      (node (ref "X2") (pin "96") (pinfunction "96_96") (pintype "passive"))
    )
    (net (code "209") (name "unconnected-(X2-Pad98)") (class "Default")
      (node (ref "X2") (pin "98") (pinfunction "98_98") (pintype "passive"))
    )
    (net (code "210") (name "unconnected-(X2-Pad100)") (class "Default")
      (node (ref "X2") (pin "100") (pinfunction "100_100") (pintype "passive"))
    )
    (net (code "211") (name "unconnected-(X2-Pad102)") (class "Default")
      (node (ref "X2") (pin "102") (pinfunction "102_102") (pintype "passive"))
    )
    (net (code "212") (name "unconnected-(X2-Pad208)") (class "Default")
      (node (ref "X2") (pin "208") (pinfunction "208_208") (pintype "passive+no_connect"))
    )
    (net (code "213") (name "unconnected-(X2-Pad210)") (class "Default")
      (node (ref "X2") (pin "210") (pinfunction "210_210") (pintype "passive+no_connect"))
    )
    (net (code "214") (name "unconnected-(X2-Pad214)") (class "Default")
      (node (ref "X2") (pin "214") (pinfunction "214_214") (pintype "passive+no_connect"))
    )
    (net (code "215") (name "unconnected-(X2-Pad216)") (class "Default")
      (node (ref "X2") (pin "216") (pinfunction "216_216") (pintype "passive+no_connect"))
    )
    (net (code "216") (name "unconnected-(X2-Pad236)") (class "Default")
      (node (ref "X2") (pin "236") (pinfunction "236_236") (pintype "passive+no_connect"))
    )
    (net (code "217") (name "unconnected-(X2-Pad238)") (class "Default")
      (node (ref "X2") (pin "238") (pinfunction "238_238") (pintype "passive+no_connect"))
    )
    (net (code "218") (name "unconnected-(X2-Pad242)") (class "Default")
      (node (ref "X2") (pin "242") (pinfunction "242_242") (pintype "passive+no_connect"))
    )
    (net (code "219") (name "unconnected-(X2-Pad244)") (class "Default")
      (node (ref "X2") (pin "244") (pinfunction "244_244") (pintype "passive+no_connect"))
    )
  )
)
